# TinyCam.net
KiCad netlist of a schematic drawn in EAGLE
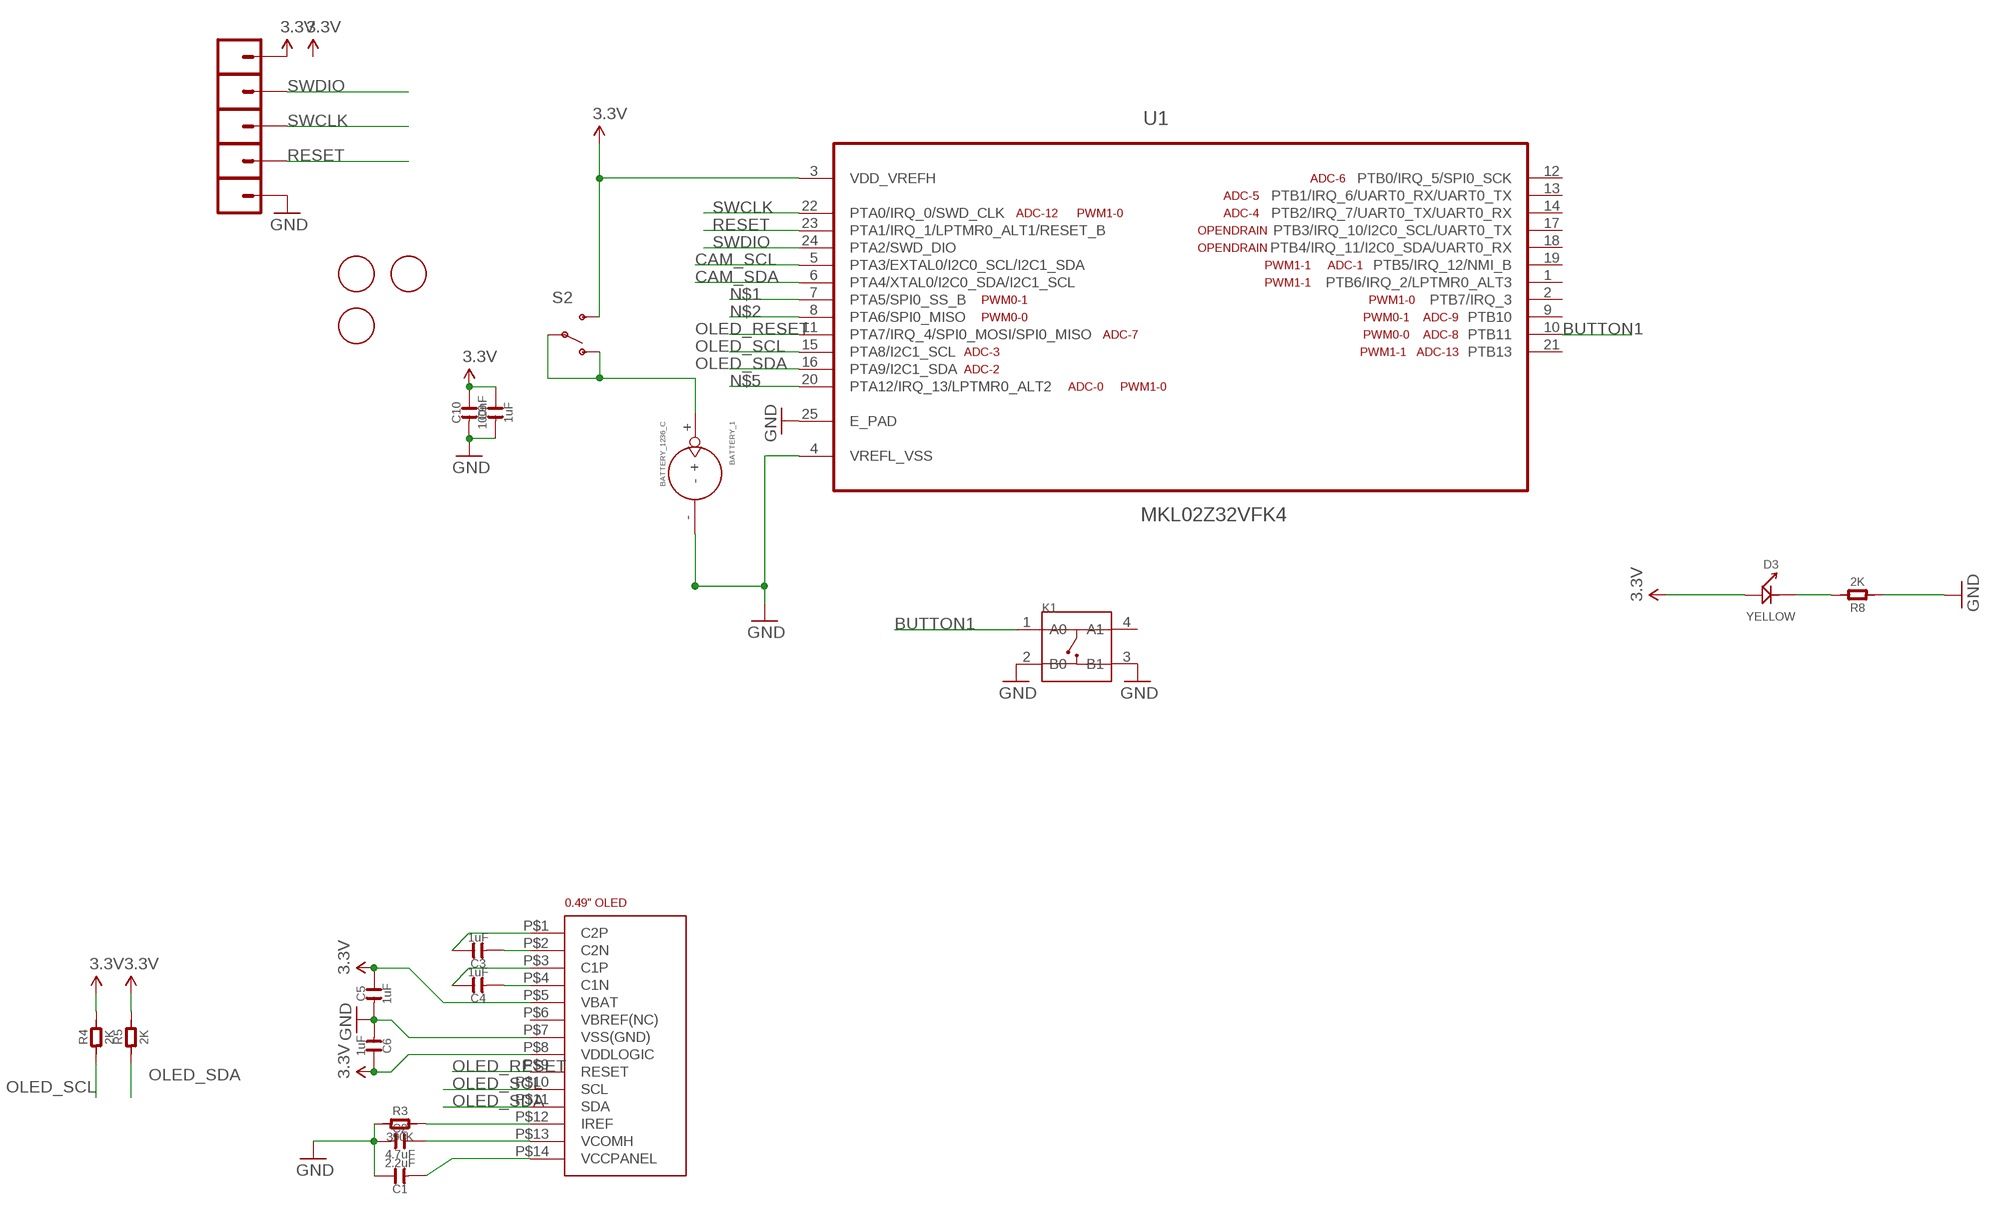
[diagram p0: schematic, sheet 1]

(export (version "E")
  (design (tool "Eeschema 10.0.6"))
  (components
    (comp (ref "BATTERY_1")
      (value "BATTERY_1236_C")
      (footprint "eagle-import:BATTERY_1236_C")
      (libsource (lib "eagle-import") (part "BATTERY_1236_C"))
    )
    (comp (ref "C1")
      (value "2.2uF")
      (footprint "eagle-import:C0603")
      (libsource (lib "eagle-import") (part "C-0603"))
    )
    (comp (ref "C2")
      (value "4.7uF")
      (footprint "eagle-import:C0603")
      (libsource (lib "eagle-import") (part "C-0603"))
    )
    (comp (ref "C3")
      (value "1uF")
      (footprint "eagle-import:C0603")
      (libsource (lib "eagle-import") (part "C-0603"))
    )
    (comp (ref "C4")
      (value "1uF")
      (footprint "eagle-import:C0603")
      (libsource (lib "eagle-import") (part "C-0603"))
    )
    (comp (ref "C5")
      (value "1uF")
      (footprint "eagle-import:C0603")
      (libsource (lib "eagle-import") (part "C-0603"))
    )
    (comp (ref "C6")
      (value "1uF")
      (footprint "eagle-import:C0603")
      (libsource (lib "eagle-import") (part "C-0603"))
    )
    (comp (ref "C9")
      (value "1uF")
      (footprint "eagle-import:C0603")
      (libsource (lib "eagle-import") (part "C-0603"))
    )
    (comp (ref "C10")
      (value "100nF")
      (footprint "eagle-import:C0603")
      (libsource (lib "eagle-import") (part "C-0603"))
    )
    (comp (ref "D3")
      (value "YELLOW")
      (footprint "eagle-import:LED0603")
      (libsource (lib "eagle-import") (part "LED"))
    )
    (comp (ref "K1")
      (value "BUTTON-4P-3100010P1")
      (footprint "eagle-import:4P-SMD-6.0X6.0X5.0H")
      (libsource (lib "eagle-import") (part "BUTTON-4P-3100010P1"))
    )
    (comp (ref "PTA6_MISO1")
      (value "M01SMD-4.5X1.5")
      (footprint "eagle-import:PAD-1.5X4.5")
      (libsource (lib "eagle-import") (part "M01SMD-4.5X1.5"))
    )
    (comp (ref "PTA6_MISO2")
      (value "M01SMD-4.5X1.5")
      (footprint "eagle-import:PAD-1.5X4.5")
      (libsource (lib "eagle-import") (part "M01SMD-4.5X1.5"))
    )
    (comp (ref "PTA6_MISO3")
      (value "M01SMD-4.5X1.5")
      (footprint "eagle-import:PAD-1.5X4.5")
      (libsource (lib "eagle-import") (part "M01SMD-4.5X1.5"))
    )
    (comp (ref "PTA6_MISO4")
      (value "M01SMD-4.5X1.5")
      (footprint "eagle-import:PAD-1.5X4.5")
      (libsource (lib "eagle-import") (part "M01SMD-4.5X1.5"))
    )
    (comp (ref "PTA6_MISO5")
      (value "M01SMD-4.5X1.5")
      (footprint "eagle-import:PAD-1.5X4.5")
      (libsource (lib "eagle-import") (part "M01SMD-4.5X1.5"))
    )
    (comp (ref "R3")
      (value "390K")
      (footprint "eagle-import:R0603")
      (libsource (lib "eagle-import") (part "R-0603"))
    )
    (comp (ref "R4")
      (value "2K")
      (footprint "eagle-import:R0603")
      (libsource (lib "eagle-import") (part "R-0603"))
    )
    (comp (ref "R5")
      (value "2K")
      (footprint "eagle-import:R0603")
      (libsource (lib "eagle-import") (part "R-0603"))
    )
    (comp (ref "R8")
      (value "2K")
      (footprint "eagle-import:R0603")
      (libsource (lib "eagle-import") (part "R-0603"))
    )
    (comp (ref "S2")
      (value "SWITCH-SPDT-SMD-A")
      (footprint "eagle-import:SWITCH-SPST-SMD-A")
      (libsource (lib "eagle-import") (part "SWITCH-SPDT-SMD-A"))
    )
    (comp (ref "U$1")
      (value "0.49\"OLEDFOLDED")
      (footprint "eagle-import:0.49_-FPC-0.7-14-FOLDED")
      (libsource (lib "eagle-import") (part "0.49{dblquote}OLEDFOLDED"))
    )
    (comp (ref "U$2")
      (value "FIDUCIAL")
      (footprint "eagle-import:FIDUCIAL_1MM")
      (libsource (lib "eagle-import") (part "FIDUCIAL"))
    )
    (comp (ref "U$3")
      (value "FIDUCIAL")
      (footprint "eagle-import:FIDUCIAL_1MM")
      (libsource (lib "eagle-import") (part "FIDUCIAL"))
    )
    (comp (ref "U$4")
      (value "FIDUCIAL")
      (footprint "eagle-import:FIDUCIAL_1MM")
      (libsource (lib "eagle-import") (part "FIDUCIAL"))
    )
    (comp (ref "U1")
      (value "MKL02Z32VFK4")
      (footprint "eagle-import:QFN50P400X400X100-25N")
      (libsource (lib "eagle-import") (part "MKL02Z32VFK4"))
    )
  )
  (nets
    (net (code "1") (name "/BUTTON1") (class "Default")
      (node (ref "K1") (pin "1") (pinfunction "A0_1") (pintype "bidirectional"))
      (node (ref "U1") (pin "10") (pinfunction "PTB11_10") (pintype "bidirectional"))
    )
    (net (code "2") (name "/CAM_SCL") (class "Default")
      (node (ref "U1") (pin "5") (pinfunction "PTA3/EXTAL0/I2C0_SCL/I2C1_SDA_5") (pintype "bidirectional"))
    )
    (net (code "3") (name "/CAM_SDA") (class "Default")
      (node (ref "U1") (pin "6") (pinfunction "PTA4/XTAL0/I2C0_SDA/I2C1_SCL_6") (pintype "bidirectional"))
    )
    (net (code "4") (name "/N$1") (class "Default")
      (node (ref "U1") (pin "7") (pinfunction "PTA5/SPI0_SS_B_7") (pintype "bidirectional"))
    )
    (net (code "5") (name "/N$2") (class "Default")
      (node (ref "U1") (pin "8") (pinfunction "PTA6/SPI0_MISO_8") (pintype "bidirectional"))
    )
    (net (code "6") (name "/N$5") (class "Default")
      (node (ref "U1") (pin "20") (pinfunction "PTA12/IRQ_13/LPTMR0_ALT2_20") (pintype "bidirectional"))
    )
    (net (code "7") (name "/OLED_RESET") (class "Default")
      (node (ref "U$1") (pin "P$9") (pinfunction "RESET_P$9") (pintype "bidirectional"))
      (node (ref "U1") (pin "11") (pinfunction "PTA7/IRQ_4/SPI0_MOSI/SPI0_MISO_11") (pintype "bidirectional"))
    )
    (net (code "8") (name "/OLED_SCL") (class "Default")
      (node (ref "R4") (pin "1") (pinfunction "1_1") (pintype "bidirectional"))
      (node (ref "U$1") (pin "P$10") (pinfunction "SCL_P$10") (pintype "bidirectional"))
      (node (ref "U1") (pin "15") (pinfunction "PTA8/I2C1_SCL_15") (pintype "bidirectional"))
    )
    (net (code "9") (name "/OLED_SDA") (class "Default")
      (node (ref "R5") (pin "1") (pinfunction "1_1") (pintype "bidirectional"))
      (node (ref "U$1") (pin "P$11") (pinfunction "SDA_P$11") (pintype "bidirectional"))
      (node (ref "U1") (pin "16") (pinfunction "PTA9/I2C1_SDA_16") (pintype "bidirectional"))
    )
    (net (code "10") (name "/RESET") (class "Default")
      (node (ref "PTA6_MISO4") (pin "P$1") (pinfunction "1_P$1") (pintype "passive"))
      (node (ref "U1") (pin "23") (pinfunction "PTA1/IRQ_1/LPTMR0_ALT1/RESET_B_23") (pintype "bidirectional"))
    )
    (net (code "11") (name "/SWCLK") (class "Default")
      (node (ref "PTA6_MISO3") (pin "P$1") (pinfunction "1_P$1") (pintype "passive"))
      (node (ref "U1") (pin "22") (pinfunction "PTA0/IRQ_0/SWD_CLK_22") (pintype "bidirectional"))
    )
    (net (code "12") (name "/SWDIO") (class "Default")
      (node (ref "PTA6_MISO2") (pin "P$1") (pinfunction "1_P$1") (pintype "passive"))
      (node (ref "U1") (pin "24") (pinfunction "PTA2/SWD_DIO_24") (pintype "bidirectional"))
    )
    (net (code "13") (name "3.3V") (class "Default")
      (node (ref "C10") (pin "2") (pinfunction "2_2") (pintype "bidirectional"))
      (node (ref "C5") (pin "2") (pinfunction "2_2") (pintype "bidirectional"))
      (node (ref "C6") (pin "2") (pinfunction "2_2") (pintype "bidirectional"))
      (node (ref "C9") (pin "2") (pinfunction "2_2") (pintype "bidirectional"))
      (node (ref "D3") (pin "+") (pinfunction "+_+") (pintype "passive"))
      (node (ref "PTA6_MISO1") (pin "P$1") (pinfunction "1_P$1") (pintype "passive"))
      (node (ref "R4") (pin "2") (pinfunction "2_2") (pintype "bidirectional"))
      (node (ref "R5") (pin "2") (pinfunction "2_2") (pintype "bidirectional"))
      (node (ref "S2") (pin "3") (pinfunction "S_3") (pintype "passive"))
      (node (ref "U$1") (pin "P$5") (pinfunction "VBAT_P$5") (pintype "bidirectional"))
      (node (ref "U$1") (pin "P$8") (pinfunction "VDDLOGIC_P$8") (pintype "bidirectional"))
      (node (ref "U1") (pin "3") (pinfunction "VDD_VREFH_3") (pintype "power_in"))
    )
    (net (code "14") (name "GND") (class "Default")
      (node (ref "BATTERY_1") (pin "-") (pinfunction "-_-") (pintype "bidirectional"))
      (node (ref "C1") (pin "2") (pinfunction "2_2") (pintype "bidirectional"))
      (node (ref "C10") (pin "1") (pinfunction "1_1") (pintype "bidirectional"))
      (node (ref "C2") (pin "1") (pinfunction "1_1") (pintype "bidirectional"))
      (node (ref "C5") (pin "1") (pinfunction "1_1") (pintype "bidirectional"))
      (node (ref "C6") (pin "1") (pinfunction "1_1") (pintype "bidirectional"))
      (node (ref "C9") (pin "1") (pinfunction "1_1") (pintype "bidirectional"))
      (node (ref "K1") (pin "2") (pinfunction "B0_2") (pintype "bidirectional"))
      (node (ref "K1") (pin "3") (pinfunction "B1_3") (pintype "bidirectional"))
      (node (ref "PTA6_MISO5") (pin "P$1") (pinfunction "1_P$1") (pintype "passive"))
      (node (ref "R3") (pin "1") (pinfunction "1_1") (pintype "bidirectional"))
      (node (ref "R8") (pin "1") (pinfunction "1_1") (pintype "bidirectional"))
      (node (ref "U$1") (pin "P$7") (pinfunction "VSS(GND)_P$7") (pintype "bidirectional"))
      (node (ref "U1") (pin "25") (pinfunction "E_PAD_25") (pintype "passive"))
      (node (ref "U1") (pin "4") (pinfunction "VREFL_VSS_4") (pintype "passive"))
    )
    (net (code "15") (name "Net-(D3-Pad-)") (class "Default")
      (node (ref "D3") (pin "-") (pinfunction "-_-") (pintype "passive"))
      (node (ref "R8") (pin "2") (pinfunction "2_2") (pintype "bidirectional"))
    )
    (net (code "16") (name "Net-(S2-O)") (class "Default")
      (node (ref "BATTERY_1") (pin "+") (pinfunction "+_+") (pintype "bidirectional"))
      (node (ref "S2") (pin "1") (pinfunction "O_1") (pintype "passive"))
      (node (ref "S2") (pin "2") (pinfunction "P_2") (pintype "passive"))
    )
    (net (code "17") (name "Net-(U$1-C1N)") (class "Default")
      (node (ref "C4") (pin "1") (pinfunction "1_1") (pintype "bidirectional"))
      (node (ref "U$1") (pin "P$4") (pinfunction "C1N_P$4") (pintype "bidirectional"))
    )
    (net (code "18") (name "Net-(U$1-C1P)") (class "Default")
      (node (ref "C4") (pin "2") (pinfunction "2_2") (pintype "bidirectional"))
      (node (ref "U$1") (pin "P$3") (pinfunction "C1P_P$3") (pintype "bidirectional"))
    )
    (net (code "19") (name "Net-(U$1-C2N)") (class "Default")
      (node (ref "C3") (pin "1") (pinfunction "1_1") (pintype "bidirectional"))
      (node (ref "U$1") (pin "P$2") (pinfunction "C2N_P$2") (pintype "bidirectional"))
    )
    (net (code "20") (name "Net-(U$1-C2P)") (class "Default")
      (node (ref "C3") (pin "2") (pinfunction "2_2") (pintype "bidirectional"))
      (node (ref "U$1") (pin "P$1") (pinfunction "C2P_P$1") (pintype "bidirectional"))
    )
    (net (code "21") (name "Net-(U$1-IREF)") (class "Default")
      (node (ref "R3") (pin "2") (pinfunction "2_2") (pintype "bidirectional"))
      (node (ref "U$1") (pin "P$12") (pinfunction "IREF_P$12") (pintype "bidirectional"))
    )
    (net (code "22") (name "Net-(U$1-VCCPANEL)") (class "Default")
      (node (ref "C1") (pin "1") (pinfunction "1_1") (pintype "bidirectional"))
      (node (ref "U$1") (pin "P$14") (pinfunction "VCCPANEL_P$14") (pintype "bidirectional"))
    )
    (net (code "23") (name "Net-(U$1-VCOMH)") (class "Default")
      (node (ref "C2") (pin "2") (pinfunction "2_2") (pintype "bidirectional"))
      (node (ref "U$1") (pin "P$13") (pinfunction "VCOMH_P$13") (pintype "bidirectional"))
    )
    (net (code "24") (name "unconnected-(K1-A1-Pad4)") (class "Default")
      (node (ref "K1") (pin "4") (pinfunction "A1_4") (pintype "bidirectional"))
    )
    (net (code "25") (name "unconnected-(U$1-VBREF(NC)-PadP$6)") (class "Default")
      (node (ref "U$1") (pin "P$6") (pinfunction "VBREF(NC)_P$6") (pintype "bidirectional"))
    )
    (net (code "26") (name "unconnected-(U1-PTB0{slash}IRQ_5{slash}SPI0_SCK-Pad12)") (class "Default")
      (node (ref "U1") (pin "12") (pinfunction "PTB0/IRQ_5/SPI0_SCK_12") (pintype "bidirectional"))
    )
    (net (code "27") (name "unconnected-(U1-PTB1{slash}IRQ_6{slash}UART0_RX{slash}UART0_TX-Pad13)") (class "Default")
      (node (ref "U1") (pin "13") (pinfunction "PTB1/IRQ_6/UART0_RX/UART0_TX_13") (pintype "bidirectional"))
    )
    (net (code "28") (name "unconnected-(U1-PTB2{slash}IRQ_7{slash}UART0_TX{slash}UART0_RX-Pad14)") (class "Default")
      (node (ref "U1") (pin "14") (pinfunction "PTB2/IRQ_7/UART0_TX/UART0_RX_14") (pintype "bidirectional"))
    )
    (net (code "29") (name "unconnected-(U1-PTB3{slash}IRQ_10{slash}I2C0_SCL{slash}UART0_TX-Pad17)") (class "Default")
      (node (ref "U1") (pin "17") (pinfunction "PTB3/IRQ_10/I2C0_SCL/UART0_TX_17") (pintype "bidirectional"))
    )
    (net (code "30") (name "unconnected-(U1-PTB4{slash}IRQ_11{slash}I2C0_SDA{slash}UART0_RX-Pad18)") (class "Default")
      (node (ref "U1") (pin "18") (pinfunction "PTB4/IRQ_11/I2C0_SDA/UART0_RX_18") (pintype "bidirectional"))
    )
    (net (code "31") (name "unconnected-(U1-PTB5{slash}IRQ_12{slash}NMI_B-Pad19)") (class "Default")
      (node (ref "U1") (pin "19") (pinfunction "PTB5/IRQ_12/NMI_B_19") (pintype "bidirectional"))
    )
    (net (code "32") (name "unconnected-(U1-PTB6{slash}IRQ_2{slash}LPTMR0_ALT3-Pad1)") (class "Default")
      (node (ref "U1") (pin "1") (pinfunction "PTB6/IRQ_2/LPTMR0_ALT3_1") (pintype "bidirectional"))
    )
    (net (code "33") (name "unconnected-(U1-PTB7{slash}IRQ_3-Pad2)") (class "Default")
      (node (ref "U1") (pin "2") (pinfunction "PTB7/IRQ_3_2") (pintype "bidirectional"))
    )
    (net (code "34") (name "unconnected-(U1-PTB10-Pad9)") (class "Default")
      (node (ref "U1") (pin "9") (pinfunction "PTB10_9") (pintype "bidirectional"))
    )
    (net (code "35") (name "unconnected-(U1-PTB13-Pad21)") (class "Default")
      (node (ref "U1") (pin "21") (pinfunction "PTB13_21") (pintype "bidirectional"))
    )
  )
)
